# XPanelNew.net
KiCad netlist of a schematic drawn in EAGLE
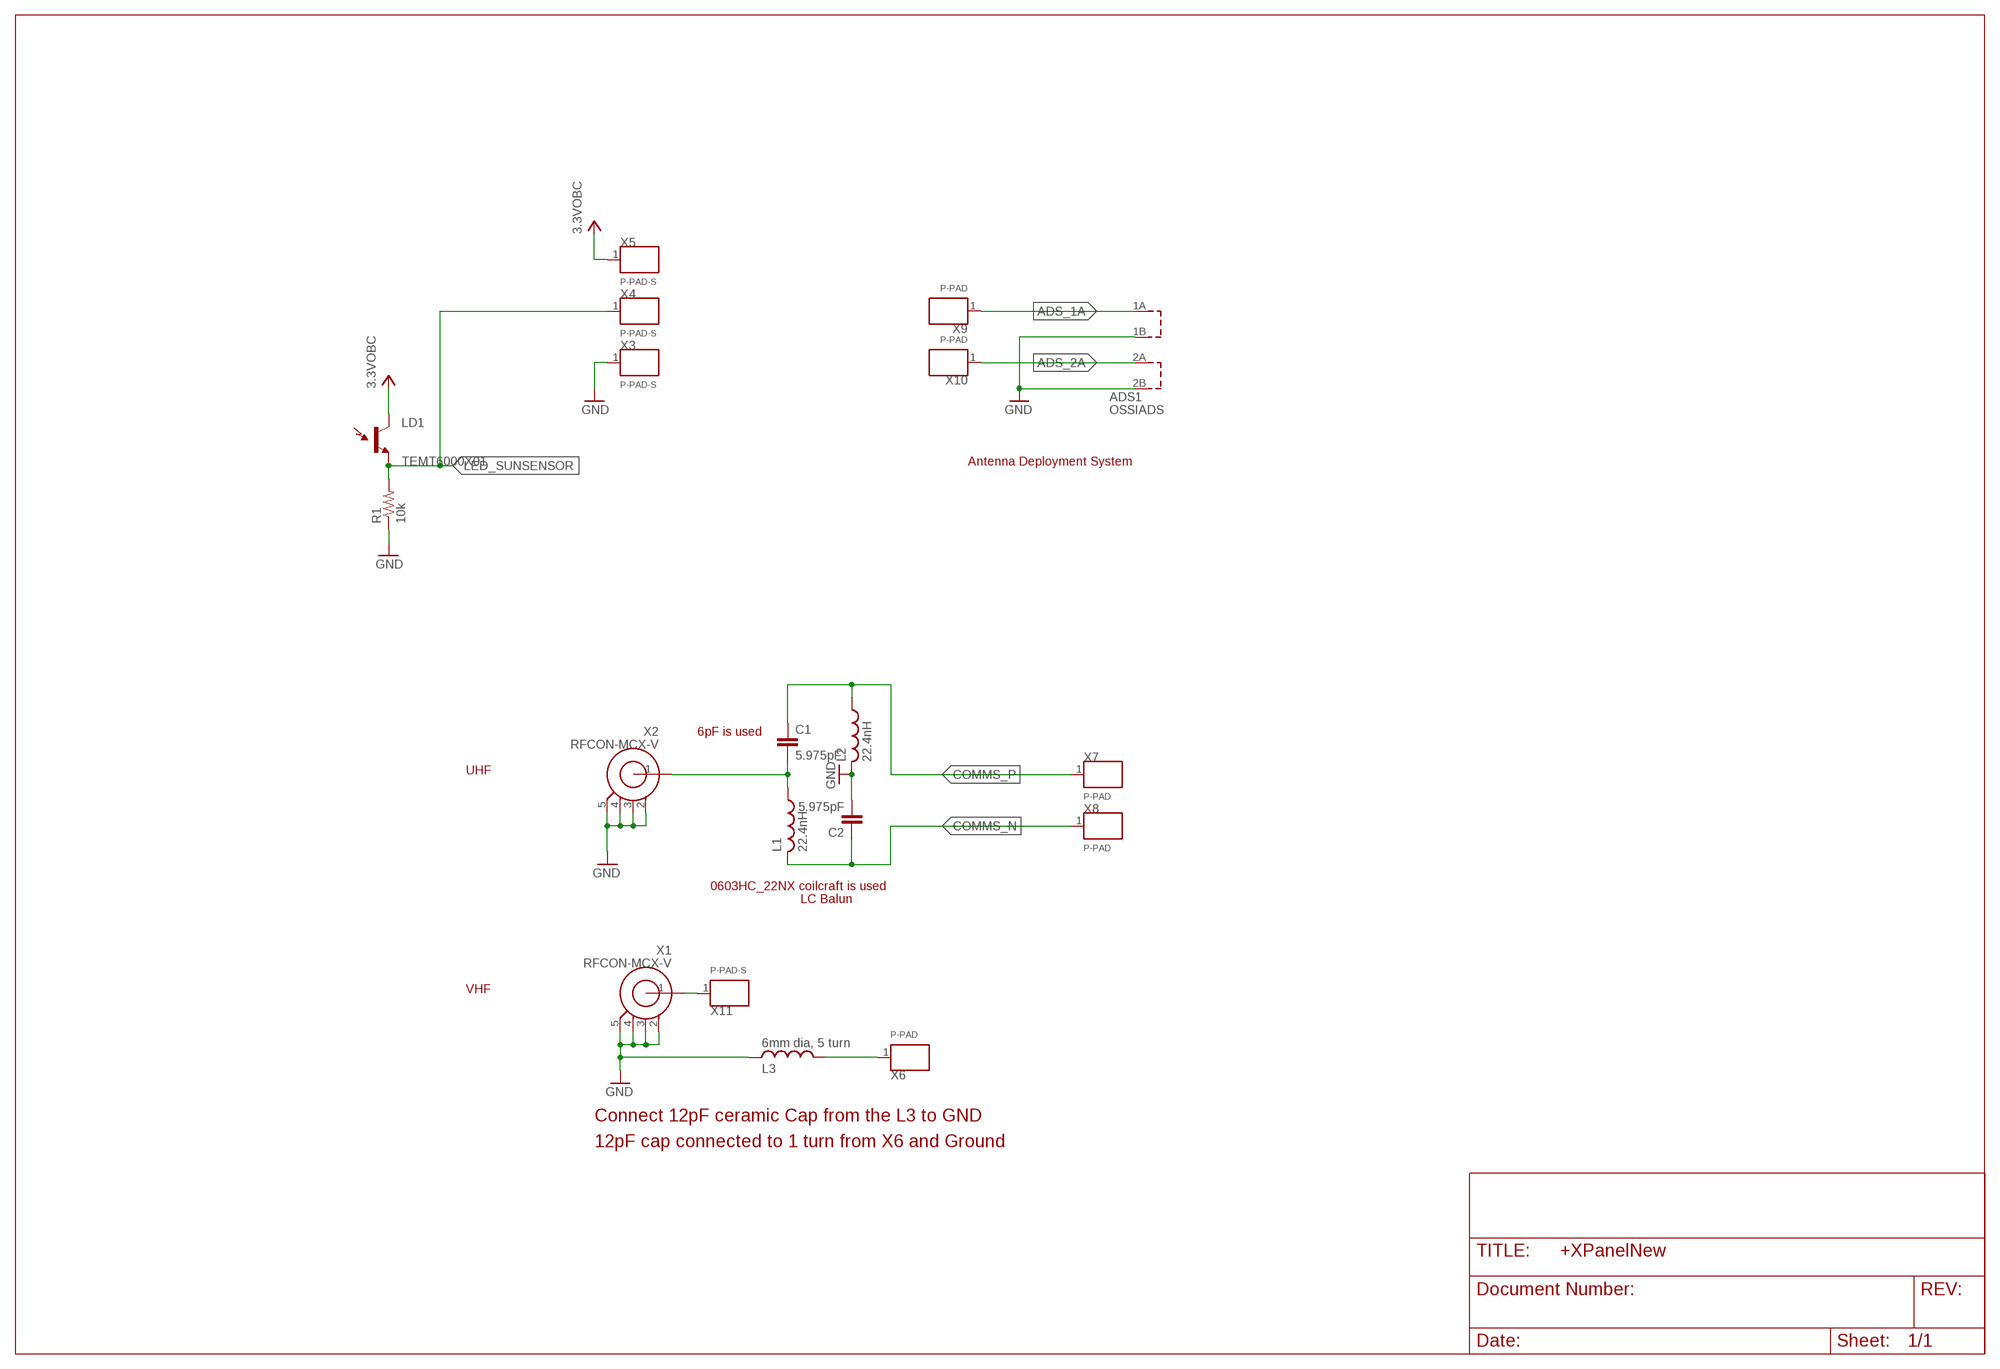
[diagram p0: schematic, sheet 1]

(export (version "E")
  (design (tool "Eeschema 10.0.6"))
  (components
    (comp (ref "ADS1")
      (value "OSSIADS")
      (footprint "eagle-import:OSSIADS")
      (libsource (lib "eagle-import") (part "OSSIADS"))
    )
    (comp (ref "C1")
      (value "5.975pF")
      (footprint "eagle-import:C0805(2012)")
      (libsource (lib "eagle-import") (part "C0805(2012)"))
    )
    (comp (ref "C2")
      (value "5.975pF")
      (footprint "eagle-import:C0805(2012)")
      (libsource (lib "eagle-import") (part "C0805(2012)"))
    )
    (comp (ref "L1")
      (value "22.4nH")
      (footprint "eagle-import:L0805(2012)")
      (libsource (lib "eagle-import") (part "L0805(2012)"))
    )
    (comp (ref "L2")
      (value "22.4nH")
      (footprint "eagle-import:L0805(2012)")
      (libsource (lib "eagle-import") (part "L0805(2012)"))
    )
    (comp (ref "L3")
      (value "6mm dia, 5 turn")
      (footprint "eagle-import:0207_10")
      (libsource (lib "eagle-import") (part "L-US0207/10"))
    )
    (comp (ref "LD1")
      (value "TEMT6000X01")
      (footprint "eagle-import:TEMT6000-SEN")
      (libsource (lib "eagle-import") (part "TEMT6000X01"))
    )
    (comp (ref "R1")
      (value "10k")
      (footprint "eagle-import:R0805(2012)")
      (libsource (lib "eagle-import") (part "R0805(2012)"))
    )
    (comp (ref "X1")
      (value "RFCON-MCX-V")
      (footprint "eagle-import:MCX-V")
      (libsource (lib "eagle-import") (part "RFCON-MCX-V"))
    )
    (comp (ref "X2")
      (value "RFCON-MCX-V")
      (footprint "eagle-import:MCX-V")
      (libsource (lib "eagle-import") (part "RFCON-MCX-V"))
    )
    (comp (ref "X3")
      (value "P-PAD-S")
      (footprint "eagle-import:P-PAD-S")
      (libsource (lib "eagle-import") (part "P-PAD-S"))
    )
    (comp (ref "X4")
      (value "P-PAD-S")
      (footprint "eagle-import:P-PAD-S")
      (libsource (lib "eagle-import") (part "P-PAD-S"))
    )
    (comp (ref "X5")
      (value "P-PAD-S")
      (footprint "eagle-import:P-PAD-S")
      (libsource (lib "eagle-import") (part "P-PAD-S"))
    )
    (comp (ref "X6")
      (value "P-PAD")
      (footprint "eagle-import:P-PAD")
      (libsource (lib "eagle-import") (part "P-PAD"))
    )
    (comp (ref "X7")
      (value "P-PAD")
      (footprint "eagle-import:P-PAD")
      (libsource (lib "eagle-import") (part "P-PAD"))
    )
    (comp (ref "X8")
      (value "P-PAD")
      (footprint "eagle-import:P-PAD")
      (libsource (lib "eagle-import") (part "P-PAD"))
    )
    (comp (ref "X9")
      (value "P-PAD")
      (footprint "eagle-import:P-PAD")
      (libsource (lib "eagle-import") (part "P-PAD"))
    )
    (comp (ref "X10")
      (value "P-PAD")
      (footprint "eagle-import:P-PAD")
      (libsource (lib "eagle-import") (part "P-PAD"))
    )
    (comp (ref "X11")
      (value "P-PAD-S")
      (footprint "eagle-import:P-PAD-S")
      (libsource (lib "eagle-import") (part "P-PAD-S"))
    )
  )
  (nets
    (net (code "1") (name "3.3VOBC") (class "Default")
      (node (ref "LD1") (pin "COLLECTOR") (pinfunction "C1_COLLECTOR") (pintype "passive"))
      (node (ref "X5") (pin "1") (pinfunction "P$1_1") (pintype "bidirectional"))
    )
    (net (code "2") (name "ADS_1A") (class "Default")
      (node (ref "ADS1") (pin "1A") (pinfunction "1A_1A") (pintype "passive"))
      (node (ref "X9") (pin "1") (pinfunction "P$1_1") (pintype "bidirectional"))
    )
    (net (code "3") (name "ADS_2A") (class "Default")
      (node (ref "ADS1") (pin "2A") (pinfunction "2A_2A") (pintype "passive"))
      (node (ref "X10") (pin "1") (pinfunction "P$1_1") (pintype "bidirectional"))
    )
    (net (code "4") (name "COMMS_N") (class "Default")
      (node (ref "C2") (pin "1") (pinfunction "1_1") (pintype "passive"))
      (node (ref "L1") (pin "2") (pinfunction "2_2") (pintype "passive"))
      (node (ref "X8") (pin "1") (pinfunction "P$1_1") (pintype "bidirectional"))
    )
    (net (code "5") (name "COMMS_P") (class "Default")
      (node (ref "C1") (pin "1") (pinfunction "1_1") (pintype "passive"))
      (node (ref "L2") (pin "1") (pinfunction "1_1") (pintype "passive"))
      (node (ref "X7") (pin "1") (pinfunction "P$1_1") (pintype "bidirectional"))
    )
    (net (code "6") (name "GND") (class "Default")
      (node (ref "ADS1") (pin "1B") (pinfunction "1B_1B") (pintype "passive"))
      (node (ref "ADS1") (pin "2B") (pinfunction "2B_2B") (pintype "passive"))
      (node (ref "C2") (pin "2") (pinfunction "2_2") (pintype "passive"))
      (node (ref "L2") (pin "2") (pinfunction "2_2") (pintype "passive"))
      (node (ref "L3") (pin "2") (pinfunction "2_2") (pintype "passive"))
      (node (ref "R1") (pin "1") (pinfunction "1_1") (pintype "passive"))
      (node (ref "X1") (pin "2") (pinfunction "2_2") (pintype "power_in"))
      (node (ref "X1") (pin "3") (pinfunction "3_3") (pintype "power_in"))
      (node (ref "X1") (pin "4") (pinfunction "4_4") (pintype "power_in"))
      (node (ref "X1") (pin "5") (pinfunction "5_5") (pintype "power_in"))
      (node (ref "X2") (pin "2") (pinfunction "2_2") (pintype "power_in"))
      (node (ref "X2") (pin "3") (pinfunction "3_3") (pintype "power_in"))
      (node (ref "X2") (pin "4") (pinfunction "4_4") (pintype "power_in"))
      (node (ref "X2") (pin "5") (pinfunction "5_5") (pintype "power_in"))
      (node (ref "X3") (pin "1") (pinfunction "P$1_1") (pintype "bidirectional"))
    )
    (net (code "7") (name "LED_SUNSENSOR") (class "Default")
      (node (ref "LD1") (pin "EMITTER") (pinfunction "E1_EMITTER") (pintype "passive"))
      (node (ref "R1") (pin "2") (pinfunction "2_2") (pintype "passive"))
      (node (ref "X4") (pin "1") (pinfunction "P$1_1") (pintype "bidirectional"))
    )
    (net (code "8") (name "Net-(C1-Pad2)") (class "Default")
      (node (ref "C1") (pin "2") (pinfunction "2_2") (pintype "passive"))
      (node (ref "L1") (pin "1") (pinfunction "1_1") (pintype "passive"))
      (node (ref "X2") (pin "1") (pinfunction "1_1") (pintype "bidirectional"))
    )
    (net (code "9") (name "Net-(X6-P$1)") (class "Default")
      (node (ref "L3") (pin "1") (pinfunction "1_1") (pintype "passive"))
      (node (ref "X6") (pin "1") (pinfunction "P$1_1") (pintype "bidirectional"))
    )
    (net (code "10") (name "Net-(X11-P$1)") (class "Default")
      (node (ref "X1") (pin "1") (pinfunction "1_1") (pintype "bidirectional"))
      (node (ref "X11") (pin "1") (pinfunction "P$1_1") (pintype "bidirectional"))
    )
  )
)
